# PRoMo_Base_CMS.net
KiCad netlist of a schematic drawn in EAGLE
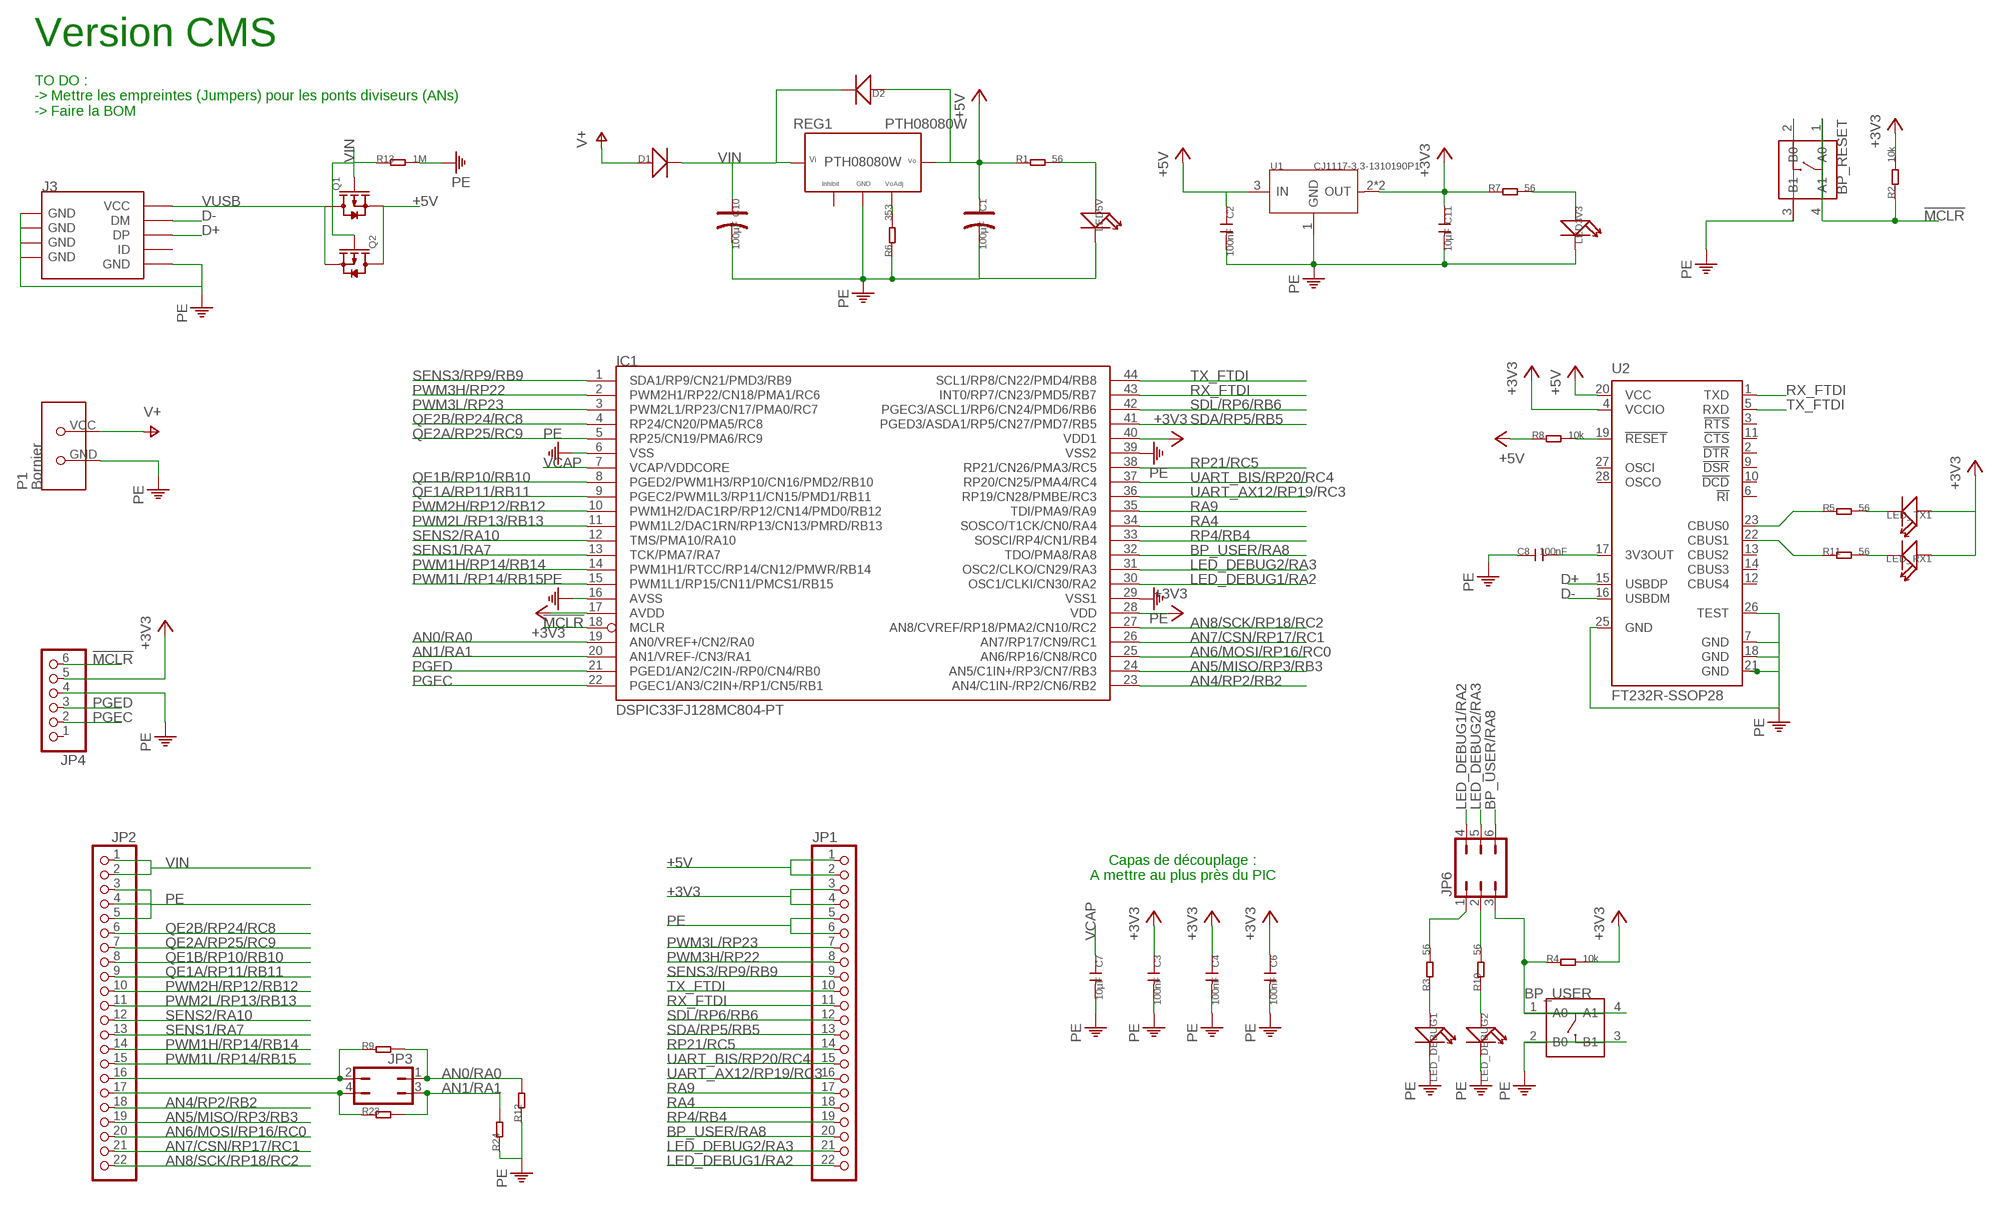
[diagram p0: schematic, sheet 1]

(export (version "E")
  (design (tool "Eeschema 10.0.6"))
  (components
    (comp (ref "BP_RESET")
      (value "BUTTON-4P-6.2X6.2")
      (footprint "eagle-import:4P-6.2X6.2")
      (libsource (lib "eagle-import") (part "BUTTON-4P-6.2X6.2"))
    )
    (comp (ref "BP_USER")
      (value "BUTTON-4P-6.2X6.2")
      (footprint "eagle-import:4P-6.2X6.2")
      (libsource (lib "eagle-import") (part "BUTTON-4P-6.2X6.2"))
    )
    (comp (ref "C1")
      (value "100µF")
      (footprint "eagle-import:ELECTRO-5.3MM")
      (libsource (lib "eagle-import") (part "CAP-D5.3/2.0"))
    )
    (comp (ref "C2")
      (value "100nF")
      (footprint "eagle-import:C0805")
      (libsource (lib "eagle-import") (part "C-0805"))
    )
    (comp (ref "C3")
      (value "100nF")
      (footprint "eagle-import:C0805")
      (libsource (lib "eagle-import") (part "C-0805"))
    )
    (comp (ref "C4")
      (value "100nF")
      (footprint "eagle-import:C0805")
      (libsource (lib "eagle-import") (part "C-0805"))
    )
    (comp (ref "C6")
      (value "100nF")
      (footprint "eagle-import:C0805")
      (libsource (lib "eagle-import") (part "C-0805"))
    )
    (comp (ref "C7")
      (value "10µF")
      (footprint "eagle-import:C0805")
      (libsource (lib "eagle-import") (part "C-0805"))
    )
    (comp (ref "C8")
      (value "100nF")
      (footprint "eagle-import:C0805")
      (libsource (lib "eagle-import") (part "C-0805"))
    )
    (comp (ref "C10")
      (value "100µF")
      (footprint "eagle-import:ELECTRO-5.3MM")
      (libsource (lib "eagle-import") (part "CAP-D5.3/2.0"))
    )
    (comp (ref "C11")
      (value "10µF")
      (footprint "eagle-import:C0805")
      (libsource (lib "eagle-import") (part "C-0805"))
    )
    (comp (ref "D1")
      (value "D'1206'")
      (footprint "eagle-import:SOD123")
      (libsource (lib "eagle-import") (part "D'1206'"))
    )
    (comp (ref "D2")
      (value "D'1206'")
      (footprint "eagle-import:SOD123")
      (libsource (lib "eagle-import") (part "D'1206'"))
    )
    (comp (ref "IC1")
      (value "DSPIC33FJ128MC804-PT")
      (footprint "eagle-import:TQFP44")
      (libsource (lib "eagle-import") (part "DSPIC33FJ128MC804-PT"))
    )
    (comp (ref "J3")
      (value "USB-MINIUSB-5P-TH")
      (footprint "eagle-import:MINI-5P")
      (libsource (lib "eagle-import") (part "USB-MINIUSB-5P-TH"))
    )
    (comp (ref "JP1")
      (value "PINHD-1X22")
      (footprint "eagle-import:1X22")
      (libsource (lib "eagle-import") (part "PINHD-1X22"))
    )
    (comp (ref "JP2")
      (value "PINHD-1X22")
      (footprint "eagle-import:1X22")
      (libsource (lib "eagle-import") (part "PINHD-1X22"))
    )
    (comp (ref "JP3")
      (value "JP2Q")
      (footprint "eagle-import:JP2Q")
      (libsource (lib "eagle-import") (part "JP2Q"))
    )
    (comp (ref "JP4")
      (value "PINHD-1X6/90")
      (footprint "eagle-import:1X06_90")
      (libsource (lib "eagle-import") (part "PINHD-1X6/90"))
    )
    (comp (ref "JP6")
      (value "JP3Q")
      (footprint "eagle-import:JP3Q")
      (libsource (lib "eagle-import") (part "JP3Q"))
    )
    (comp (ref "LED3V3")
      (value "LED'1206'")
      (footprint "eagle-import:LED-1206")
      (libsource (lib "eagle-import") (part "LED'1206'"))
    )
    (comp (ref "LED5V")
      (value "LED'1206'")
      (footprint "eagle-import:LED-1206")
      (libsource (lib "eagle-import") (part "LED'1206'"))
    )
    (comp (ref "LED_DEBUG1")
      (value "LED'1206'")
      (footprint "eagle-import:LED-1206")
      (libsource (lib "eagle-import") (part "LED'1206'"))
    )
    (comp (ref "LED_DEBUG2")
      (value "LED'1206'")
      (footprint "eagle-import:LED-1206")
      (libsource (lib "eagle-import") (part "LED'1206'"))
    )
    (comp (ref "LED_RX1")
      (value "LED'1206'")
      (footprint "eagle-import:LED-1206")
      (libsource (lib "eagle-import") (part "LED'1206'"))
    )
    (comp (ref "LED_TX1")
      (value "LED'1206'")
      (footprint "eagle-import:LED-1206")
      (libsource (lib "eagle-import") (part "LED'1206'"))
    )
    (comp (ref "P1")
      (value "Bornier")
      (footprint "eagle-import:BORNIER_COUDEE_3.5")
      (libsource (lib "eagle-import") (part "BORNIER_3.5MM"))
    )
    (comp (ref "Q1")
      (value "MOSFET-P'SI2323CDS/SI2305DS<BR>'")
      (footprint "eagle-import:SOT23")
      (libsource (lib "eagle-import") (part "MOSFET-P'SI2323CDS/SI2305DS{lt}BR{gt}'"))
    )
    (comp (ref "Q2")
      (value "MOSFET-P'SI2323CDS/SI2305DS<BR>'")
      (footprint "eagle-import:SOT23")
      (libsource (lib "eagle-import") (part "MOSFET-P'SI2323CDS/SI2305DS{lt}BR{gt}'"))
    )
    (comp (ref "R1")
      (value "56")
      (footprint "eagle-import:R0805")
      (libsource (lib "eagle-import") (part "R-0805"))
    )
    (comp (ref "R2")
      (value "10k")
      (footprint "eagle-import:R0805")
      (libsource (lib "eagle-import") (part "R-0805"))
    )
    (comp (ref "R3")
      (value "56")
      (footprint "eagle-import:R0805")
      (libsource (lib "eagle-import") (part "R-0805"))
    )
    (comp (ref "R4")
      (value "10k")
      (footprint "eagle-import:R0805")
      (libsource (lib "eagle-import") (part "R-0805"))
    )
    (comp (ref "R5")
      (value "56")
      (footprint "eagle-import:R0805")
      (libsource (lib "eagle-import") (part "R-0805"))
    )
    (comp (ref "R6")
      (value "353")
      (footprint "eagle-import:R0204_7")
      (libsource (lib "eagle-import") (part "R-0204/7"))
    )
    (comp (ref "R7")
      (value "56")
      (footprint "eagle-import:R0805")
      (libsource (lib "eagle-import") (part "R-0805"))
    )
    (comp (ref "R8")
      (value "10k")
      (footprint "eagle-import:R0805")
      (libsource (lib "eagle-import") (part "R-0805"))
    )
    (comp (ref "R9")
      (value "R-0805")
      (footprint "eagle-import:R0805")
      (libsource (lib "eagle-import") (part "R-0805"))
    )
    (comp (ref "R10")
      (value "56")
      (footprint "eagle-import:R0805")
      (libsource (lib "eagle-import") (part "R-0805"))
    )
    (comp (ref "R11")
      (value "56")
      (footprint "eagle-import:R0805")
      (libsource (lib "eagle-import") (part "R-0805"))
    )
    (comp (ref "R12")
      (value "R-0805")
      (footprint "eagle-import:R0805")
      (libsource (lib "eagle-import") (part "R-0805"))
    )
    (comp (ref "R13")
      (value "1M")
      (footprint "eagle-import:R0805")
      (libsource (lib "eagle-import") (part "R-0805"))
    )
    (comp (ref "R23")
      (value "R-0805")
      (footprint "eagle-import:R0805")
      (libsource (lib "eagle-import") (part "R-0805"))
    )
    (comp (ref "R24")
      (value "R-0805")
      (footprint "eagle-import:R0805")
      (libsource (lib "eagle-import") (part "R-0805"))
    )
    (comp (ref "REG1")
      (value "PTH08080W")
      (footprint "eagle-import:PTH08080W")
      (libsource (lib "eagle-import") (part "PTH08080W"))
    )
    (comp (ref "U1")
      (value "CJ1117-3.3-1310190P1")
      (footprint "eagle-import:SOT223")
      (libsource (lib "eagle-import") (part "CJ1117-3.3-1310190P1"))
    )
    (comp (ref "U2")
      (value "FT232R-SSOP28")
      (footprint "eagle-import:SSOP28")
      (libsource (lib "eagle-import") (part "FT232R-SSOP28"))
    )
  )
  (nets
    (net (code "1") (name "+3V3") (class "Default")
      (node (ref "C11") (pin "1") (pinfunction "1_1") (pintype "passive"))
      (node (ref "C3") (pin "1") (pinfunction "1_1") (pintype "passive"))
      (node (ref "C4") (pin "1") (pinfunction "1_1") (pintype "passive"))
      (node (ref "C6") (pin "1") (pinfunction "1_1") (pintype "passive"))
      (node (ref "IC1") (pin "17") (pinfunction "AVDD_17") (pintype "power_in"))
      (node (ref "IC1") (pin "28") (pinfunction "VDD_28") (pintype "power_in"))
      (node (ref "IC1") (pin "40") (pinfunction "VDD1_40") (pintype "power_in"))
      (node (ref "JP1") (pin "3") (pinfunction "3_3") (pintype "passive"))
      (node (ref "JP1") (pin "4") (pinfunction "4_4") (pintype "passive"))
      (node (ref "JP4") (pin "5") (pinfunction "5_5") (pintype "passive"))
      (node (ref "LED_RX1") (pin "+") (pinfunction "+_+") (pintype "passive"))
      (node (ref "LED_TX1") (pin "+") (pinfunction "+_+") (pintype "passive"))
      (node (ref "R2") (pin "2") (pinfunction "2_2") (pintype "passive"))
      (node (ref "R4") (pin "2") (pinfunction "2_2") (pintype "passive"))
      (node (ref "R7") (pin "1") (pinfunction "1_1") (pintype "passive"))
      (node (ref "U1") (pin "2") (pinfunction "OUT_2") (pintype "bidirectional"))
      (node (ref "U1") (pin "TER") (pinfunction "OUT_TER") (pintype "bidirectional"))
      (node (ref "U2") (pin "4") (pinfunction "VCCIO_4") (pintype "input"))
    )
    (net (code "2") (name "+5V") (class "Default")
      (node (ref "C1") (pin "+") (pinfunction "+_+") (pintype "passive"))
      (node (ref "C2") (pin "1") (pinfunction "1_1") (pintype "passive"))
      (node (ref "D2") (pin "+") (pinfunction "+_+") (pintype "passive"))
      (node (ref "JP1") (pin "1") (pinfunction "1_1") (pintype "passive"))
      (node (ref "JP1") (pin "2") (pinfunction "2_2") (pintype "passive"))
      (node (ref "Q1") (pin "2") (pinfunction "S_2") (pintype "passive"))
      (node (ref "Q2") (pin "3") (pinfunction "D_3") (pintype "passive"))
      (node (ref "R1") (pin "1") (pinfunction "1_1") (pintype "passive"))
      (node (ref "R8") (pin "1") (pinfunction "1_1") (pintype "passive"))
      (node (ref "REG1") (pin "P$3") (pinfunction "3_VO_P$3") (pintype "bidirectional"))
      (node (ref "U1") (pin "3") (pinfunction "IN_3") (pintype "bidirectional"))
      (node (ref "U2") (pin "20") (pinfunction "VCC_20") (pintype "input"))
    )
    (net (code "3") (name "/AN0{slash}RA0") (class "Default")
      (node (ref "IC1") (pin "19") (pinfunction "AN0/VREF+/CN2/RA0_19") (pintype "bidirectional"))
      (node (ref "JP3") (pin "1") (pinfunction "1_1") (pintype "passive"))
      (node (ref "R12") (pin "2") (pinfunction "2_2") (pintype "passive"))
      (node (ref "R9") (pin "2") (pinfunction "2_2") (pintype "passive"))
    )
    (net (code "4") (name "/AN1{slash}RA1") (class "Default")
      (node (ref "IC1") (pin "20") (pinfunction "AN1/VREF-/CN3/RA1_20") (pintype "bidirectional"))
      (node (ref "JP3") (pin "3") (pinfunction "3_3") (pintype "passive"))
      (node (ref "R23") (pin "2") (pinfunction "2_2") (pintype "passive"))
      (node (ref "R24") (pin "2") (pinfunction "2_2") (pintype "passive"))
    )
    (net (code "5") (name "/AN4{slash}RP2{slash}RB2") (class "Default")
      (node (ref "IC1") (pin "23") (pinfunction "AN4/C1IN-/RP2/CN6/RB2_23") (pintype "bidirectional"))
      (node (ref "JP2") (pin "18") (pinfunction "18_18") (pintype "passive"))
    )
    (net (code "6") (name "/AN5{slash}MISO{slash}RP3{slash}RB3") (class "Default")
      (node (ref "IC1") (pin "24") (pinfunction "AN5/C1IN+/RP3/CN7/RB3_24") (pintype "bidirectional"))
      (node (ref "JP2") (pin "19") (pinfunction "19_19") (pintype "passive"))
    )
    (net (code "7") (name "/AN6{slash}MOSI{slash}RP16{slash}RC0") (class "Default")
      (node (ref "IC1") (pin "25") (pinfunction "AN6/RP16/CN8/RC0_25") (pintype "bidirectional"))
      (node (ref "JP2") (pin "20") (pinfunction "20_20") (pintype "passive"))
    )
    (net (code "8") (name "/AN7{slash}CSN{slash}RP17{slash}RC1") (class "Default")
      (node (ref "IC1") (pin "26") (pinfunction "AN7/RP17/CN9/RC1_26") (pintype "bidirectional"))
      (node (ref "JP2") (pin "21") (pinfunction "21_21") (pintype "passive"))
    )
    (net (code "9") (name "/AN8{slash}SCK{slash}RP18{slash}RC2") (class "Default")
      (node (ref "IC1") (pin "27") (pinfunction "AN8/CVREF/RP18/PMA2/CN10/RC2_27") (pintype "bidirectional"))
      (node (ref "JP2") (pin "22") (pinfunction "22_22") (pintype "passive"))
    )
    (net (code "10") (name "/BP_USER{slash}RA8") (class "Default")
      (node (ref "IC1") (pin "32") (pinfunction "TDO/PMA8/RA8_32") (pintype "bidirectional"))
      (node (ref "JP1") (pin "20") (pinfunction "20_20") (pintype "passive"))
      (node (ref "JP6") (pin "6") (pinfunction "6_6") (pintype "passive"))
    )
    (net (code "11") (name "/D+") (class "Default")
      (node (ref "J3") (pin "DP") (pinfunction "DP_DP") (pintype "bidirectional"))
      (node (ref "U2") (pin "15") (pinfunction "USBDP_15") (pintype "input"))
    )
    (net (code "12") (name "/D-") (class "Default")
      (node (ref "J3") (pin "DM") (pinfunction "DM_DM") (pintype "bidirectional"))
      (node (ref "U2") (pin "16") (pinfunction "USBDM_16") (pintype "input"))
    )
    (net (code "13") (name "/LED_DEBUG1{slash}RA2") (class "Default")
      (node (ref "IC1") (pin "30") (pinfunction "OSC1/CLKI/CN30/RA2_30") (pintype "bidirectional"))
      (node (ref "JP1") (pin "22") (pinfunction "22_22") (pintype "passive"))
      (node (ref "JP6") (pin "4") (pinfunction "4_4") (pintype "passive"))
    )
    (net (code "14") (name "/LED_DEBUG2{slash}RA3") (class "Default")
      (node (ref "IC1") (pin "31") (pinfunction "OSC2/CLKO/CN29/RA3_31") (pintype "bidirectional"))
      (node (ref "JP1") (pin "21") (pinfunction "21_21") (pintype "passive"))
      (node (ref "JP6") (pin "5") (pinfunction "5_5") (pintype "passive"))
    )
    (net (code "15") (name "/PGEC") (class "Default")
      (node (ref "IC1") (pin "22") (pinfunction "PGEC1/AN3/C2IN+/RP1/CN5/RB1_22") (pintype "bidirectional"))
      (node (ref "JP4") (pin "2") (pinfunction "2_2") (pintype "passive"))
    )
    (net (code "16") (name "/PGED") (class "Default")
      (node (ref "IC1") (pin "21") (pinfunction "PGED1/AN2/C2IN-/RP0/CN4/RB0_21") (pintype "bidirectional"))
      (node (ref "JP4") (pin "3") (pinfunction "3_3") (pintype "passive"))
    )
    (net (code "17") (name "/PWM1H{slash}RP14{slash}RB14") (class "Default")
      (node (ref "IC1") (pin "14") (pinfunction "PWM1H1/RTCC/RP14/CN12/PMWR/RB14_14") (pintype "bidirectional"))
      (node (ref "JP2") (pin "14") (pinfunction "14_14") (pintype "passive"))
    )
    (net (code "18") (name "/PWM1L{slash}RP14{slash}RB15") (class "Default")
      (node (ref "IC1") (pin "15") (pinfunction "PWM1L1/RP15/CN11/PMCS1/RB15_15") (pintype "bidirectional"))
      (node (ref "JP2") (pin "15") (pinfunction "15_15") (pintype "passive"))
    )
    (net (code "19") (name "/PWM2H{slash}RP12{slash}RB12") (class "Default")
      (node (ref "IC1") (pin "10") (pinfunction "PWM1H2/DAC1RP/RP12/CN14/PMD0/RB12_10") (pintype "bidirectional"))
      (node (ref "JP2") (pin "10") (pinfunction "10_10") (pintype "passive"))
    )
    (net (code "20") (name "/PWM2L{slash}RP13{slash}RB13") (class "Default")
      (node (ref "IC1") (pin "11") (pinfunction "PWM1L2/DAC1RN/RP13/CN13/PMRD/RB13_11") (pintype "bidirectional"))
      (node (ref "JP2") (pin "11") (pinfunction "11_11") (pintype "passive"))
    )
    (net (code "21") (name "/PWM3H{slash}RP22") (class "Default")
      (node (ref "IC1") (pin "2") (pinfunction "PWM2H1/RP22/CN18/PMA1/RC6_2") (pintype "bidirectional"))
      (node (ref "JP1") (pin "8") (pinfunction "8_8") (pintype "passive"))
    )
    (net (code "22") (name "/PWM3L{slash}RP23") (class "Default")
      (node (ref "IC1") (pin "3") (pinfunction "PWM2L1/RP23/CN17/PMA0/RC7_3") (pintype "bidirectional"))
      (node (ref "JP1") (pin "7") (pinfunction "7_7") (pintype "passive"))
    )
    (net (code "23") (name "/QE1A{slash}RP11{slash}RB11") (class "Default")
      (node (ref "IC1") (pin "9") (pinfunction "PGEC2/PWM1L3/RP11/CN15/PMD1/RB11_9") (pintype "bidirectional"))
      (node (ref "JP2") (pin "9") (pinfunction "9_9") (pintype "passive"))
    )
    (net (code "24") (name "/QE1B{slash}RP10{slash}RB10") (class "Default")
      (node (ref "IC1") (pin "8") (pinfunction "PGED2/PWM1H3/RP10/CN16/PMD2/RB10_8") (pintype "bidirectional"))
      (node (ref "JP2") (pin "8") (pinfunction "8_8") (pintype "passive"))
    )
    (net (code "25") (name "/QE2A{slash}RP25{slash}RC9") (class "Default")
      (node (ref "IC1") (pin "5") (pinfunction "RP25/CN19/PMA6/RC9_5") (pintype "bidirectional"))
      (node (ref "JP2") (pin "7") (pinfunction "7_7") (pintype "passive"))
    )
    (net (code "26") (name "/QE2B{slash}RP24{slash}RC8") (class "Default")
      (node (ref "IC1") (pin "4") (pinfunction "RP24/CN20/PMA5/RC8_4") (pintype "bidirectional"))
      (node (ref "JP2") (pin "6") (pinfunction "6_6") (pintype "passive"))
    )
    (net (code "27") (name "/RA4") (class "Default")
      (node (ref "IC1") (pin "34") (pinfunction "SOSCO/T1CK/CN0/RA4_34") (pintype "bidirectional"))
      (node (ref "JP1") (pin "18") (pinfunction "18_18") (pintype "passive"))
    )
    (net (code "28") (name "/RA9") (class "Default")
      (node (ref "IC1") (pin "35") (pinfunction "TDI/PMA9/RA9_35") (pintype "bidirectional"))
      (node (ref "JP1") (pin "17") (pinfunction "17_17") (pintype "passive"))
    )
    (net (code "29") (name "/RP4{slash}RB4") (class "Default")
      (node (ref "IC1") (pin "33") (pinfunction "SOSCI/RP4/CN1/RB4_33") (pintype "bidirectional"))
      (node (ref "JP1") (pin "19") (pinfunction "19_19") (pintype "passive"))
    )
    (net (code "30") (name "/RP21{slash}RC5") (class "Default")
      (node (ref "IC1") (pin "38") (pinfunction "RP21/CN26/PMA3/RC5_38") (pintype "bidirectional"))
      (node (ref "JP1") (pin "14") (pinfunction "14_14") (pintype "passive"))
    )
    (net (code "31") (name "/RX_FTDI") (class "Default")
      (node (ref "IC1") (pin "43") (pinfunction "INT0/RP7/CN23/PMD5/RB7_43") (pintype "bidirectional"))
      (node (ref "JP1") (pin "11") (pinfunction "11_11") (pintype "passive"))
      (node (ref "U2") (pin "1") (pinfunction "TXD_1") (pintype "input"))
    )
    (net (code "32") (name "/SDA{slash}RP5{slash}RB5") (class "Default")
      (node (ref "IC1") (pin "41") (pinfunction "PGED3/ASDA1/RP5/CN27/PMD7/RB5_41") (pintype "bidirectional"))
      (node (ref "JP1") (pin "13") (pinfunction "13_13") (pintype "passive"))
    )
    (net (code "33") (name "/SDL{slash}RP6{slash}RB6") (class "Default")
      (node (ref "IC1") (pin "42") (pinfunction "PGEC3/ASCL1/RP6/CN24/PMD6/RB6_42") (pintype "bidirectional"))
      (node (ref "JP1") (pin "12") (pinfunction "12_12") (pintype "passive"))
    )
    (net (code "34") (name "/SENS1{slash}RA7") (class "Default")
      (node (ref "IC1") (pin "13") (pinfunction "TCK/PMA7/RA7_13") (pintype "bidirectional"))
      (node (ref "JP2") (pin "13") (pinfunction "13_13") (pintype "passive"))
    )
    (net (code "35") (name "/SENS2{slash}RA10") (class "Default")
      (node (ref "IC1") (pin "12") (pinfunction "TMS/PMA10/RA10_12") (pintype "bidirectional"))
      (node (ref "JP2") (pin "12") (pinfunction "12_12") (pintype "passive"))
    )
    (net (code "36") (name "/SENS3{slash}RP9{slash}RB9") (class "Default")
      (node (ref "IC1") (pin "1") (pinfunction "SDA1/RP9/CN21/PMD3/RB9_1") (pintype "bidirectional"))
      (node (ref "JP1") (pin "9") (pinfunction "9_9") (pintype "passive"))
    )
    (net (code "37") (name "/TX_FTDI") (class "Default")
      (node (ref "IC1") (pin "44") (pinfunction "SCL1/RP8/CN22/PMD4/RB8_44") (pintype "bidirectional"))
      (node (ref "JP1") (pin "10") (pinfunction "10_10") (pintype "passive"))
      (node (ref "U2") (pin "5") (pinfunction "RXD_5") (pintype "input"))
    )
    (net (code "38") (name "/UART_AX12{slash}RP19{slash}RC3") (class "Default")
      (node (ref "IC1") (pin "36") (pinfunction "RP19/CN28/PMBE/RC3_36") (pintype "bidirectional"))
      (node (ref "JP1") (pin "16") (pinfunction "16_16") (pintype "passive"))
    )
    (net (code "39") (name "/UART_BIS{slash}RP20{slash}RC4") (class "Default")
      (node (ref "IC1") (pin "37") (pinfunction "RP20/CN25/PMA4/RC4_37") (pintype "bidirectional"))
      (node (ref "JP1") (pin "15") (pinfunction "15_15") (pintype "passive"))
    )
    (net (code "40") (name "/VCAP") (class "Default")
      (node (ref "C7") (pin "1") (pinfunction "1_1") (pintype "passive"))
      (node (ref "IC1") (pin "7") (pinfunction "VCAP/VDDCORE_7") (pintype "power_in"))
    )
    (net (code "41") (name "/VIN") (class "Default")
      (node (ref "C10") (pin "+") (pinfunction "+_+") (pintype "passive"))
      (node (ref "D1") (pin "-") (pinfunction "-_-") (pintype "passive"))
      (node (ref "D2") (pin "-") (pinfunction "-_-") (pintype "passive"))
      (node (ref "JP2") (pin "1") (pinfunction "1_1") (pintype "passive"))
      (node (ref "JP2") (pin "2") (pinfunction "2_2") (pintype "passive"))
      (node (ref "Q1") (pin "1") (pinfunction "G_1") (pintype "passive"))
      (node (ref "Q2") (pin "1") (pinfunction "G_1") (pintype "passive"))
      (node (ref "R13") (pin "1") (pinfunction "1_1") (pintype "passive"))
      (node (ref "REG1") (pin "P$1") (pinfunction "1_VI_P$1") (pintype "bidirectional"))
    )
    (net (code "42") (name "/VUSB") (class "Default")
      (node (ref "J3") (pin "VCC") (pinfunction "VCC_VCC") (pintype "bidirectional"))
      (node (ref "Q1") (pin "3") (pinfunction "D_3") (pintype "passive"))
      (node (ref "Q2") (pin "2") (pinfunction "S_2") (pintype "passive"))
    )
    (net (code "43") (name "/~{MCLR}") (class "Default")
      (node (ref "BP_RESET") (pin "1") (pinfunction "A0_1") (pintype "bidirectional"))
      (node (ref "BP_RESET") (pin "4") (pinfunction "A1_4") (pintype "bidirectional"))
      (node (ref "IC1") (pin "18") (pinfunction "MCLR_18") (pintype "input"))
      (node (ref "JP4") (pin "6") (pinfunction "6_6") (pintype "passive"))
      (node (ref "R2") (pin "1") (pinfunction "1_1") (pintype "passive"))
    )
    (net (code "44") (name "Net-(BP_USER-A0)") (class "Default")
      (node (ref "BP_USER") (pin "1") (pinfunction "A0_1") (pintype "bidirectional"))
      (node (ref "BP_USER") (pin "4") (pinfunction "A1_4") (pintype "bidirectional"))
      (node (ref "JP6") (pin "3") (pinfunction "3_3") (pintype "passive"))
      (node (ref "R4") (pin "1") (pinfunction "1_1") (pintype "passive"))
    )
    (net (code "45") (name "Net-(JP2-Pad16)") (class "Default")
      (node (ref "JP2") (pin "16") (pinfunction "16_16") (pintype "passive"))
      (node (ref "JP3") (pin "2") (pinfunction "2_2") (pintype "passive"))
      (node (ref "R9") (pin "1") (pinfunction "1_1") (pintype "passive"))
    )
    (net (code "46") (name "Net-(JP2-Pad17)") (class "Default")
      (node (ref "JP2") (pin "17") (pinfunction "17_17") (pintype "passive"))
      (node (ref "JP3") (pin "4") (pinfunction "4_4") (pintype "passive"))
      (node (ref "R23") (pin "1") (pinfunction "1_1") (pintype "passive"))
    )
    (net (code "47") (name "Net-(JP6-Pad1)") (class "Default")
      (node (ref "JP6") (pin "1") (pinfunction "1_1") (pintype "passive"))
      (node (ref "R3") (pin "2") (pinfunction "2_2") (pintype "passive"))
    )
    (net (code "48") (name "Net-(JP6-Pad2)") (class "Default")
      (node (ref "JP6") (pin "2") (pinfunction "2_2") (pintype "passive"))
      (node (ref "R10") (pin "2") (pinfunction "2_2") (pintype "passive"))
    )
    (net (code "49") (name "Net-(LED3V3-Pad+)") (class "Default")
      (node (ref "LED3V3") (pin "+") (pinfunction "+_+") (pintype "passive"))
      (node (ref "R7") (pin "2") (pinfunction "2_2") (pintype "passive"))
    )
    (net (code "50") (name "Net-(LED5V-Pad+)") (class "Default")
      (node (ref "LED5V") (pin "+") (pinfunction "+_+") (pintype "passive"))
      (node (ref "R1") (pin "2") (pinfunction "2_2") (pintype "passive"))
    )
    (net (code "51") (name "Net-(LED_DEBUG1-Pad+)") (class "Default")
      (node (ref "LED_DEBUG1") (pin "+") (pinfunction "+_+") (pintype "passive"))
      (node (ref "R3") (pin "1") (pinfunction "1_1") (pintype "passive"))
    )
    (net (code "52") (name "Net-(LED_DEBUG2-Pad+)") (class "Default")
      (node (ref "LED_DEBUG2") (pin "+") (pinfunction "+_+") (pintype "passive"))
      (node (ref "R10") (pin "1") (pinfunction "1_1") (pintype "passive"))
    )
    (net (code "53") (name "Net-(LED_RX1-Pad-)") (class "Default")
      (node (ref "LED_RX1") (pin "-") (pinfunction "-_-") (pintype "passive"))
      (node (ref "R11") (pin "2") (pinfunction "2_2") (pintype "passive"))
    )
    (net (code "54") (name "Net-(LED_TX1-Pad-)") (class "Default")
      (node (ref "LED_TX1") (pin "-") (pinfunction "-_-") (pintype "passive"))
      (node (ref "R5") (pin "2") (pinfunction "2_2") (pintype "passive"))
    )
    (net (code "55") (name "Net-(REG1-4_VOADJ)") (class "Default")
      (node (ref "R6") (pin "2") (pinfunction "2_2") (pintype "passive"))
      (node (ref "REG1") (pin "P$4") (pinfunction "4_VOADJ_P$4") (pintype "bidirectional"))
    )
    (net (code "56") (name "Net-(U2-3V3OUT)") (class "Default")
      (node (ref "C8") (pin "2") (pinfunction "2_2") (pintype "passive"))
      (node (ref "U2") (pin "17") (pinfunction "3V3OUT_17") (pintype "input"))
    )
    (net (code "57") (name "Net-(U2-CBUS0)") (class "Default")
      (node (ref "R5") (pin "1") (pinfunction "1_1") (pintype "passive"))
      (node (ref "U2") (pin "23") (pinfunction "CBUS0_23") (pintype "input"))
    )
    (net (code "58") (name "Net-(U2-CBUS1)") (class "Default")
      (node (ref "R11") (pin "1") (pinfunction "1_1") (pintype "passive"))
      (node (ref "U2") (pin "22") (pinfunction "CBUS1_22") (pintype "input"))
    )
    (net (code "59") (name "Net-(U2-~{RESET})") (class "Default")
      (node (ref "R8") (pin "2") (pinfunction "2_2") (pintype "passive"))
      (node (ref "U2") (pin "19") (pinfunction "~{RESET}_19") (pintype "input"))
    )
    (net (code "60") (name "PE") (class "Default")
      (node (ref "BP_RESET") (pin "2") (pinfunction "B0_2") (pintype "bidirectional"))
      (node (ref "BP_RESET") (pin "3") (pinfunction "B1_3") (pintype "bidirectional"))
      (node (ref "BP_USER") (pin "2") (pinfunction "B0_2") (pintype "bidirectional"))
      (node (ref "BP_USER") (pin "3") (pinfunction "B1_3") (pintype "bidirectional"))
      (node (ref "C1") (pin "-") (pinfunction "-_-") (pintype "passive"))
      (node (ref "C10") (pin "-") (pinfunction "-_-") (pintype "passive"))
      (node (ref "C11") (pin "2") (pinfunction "2_2") (pintype "passive"))
      (node (ref "C2") (pin "2") (pinfunction "2_2") (pintype "passive"))
      (node (ref "C3") (pin "2") (pinfunction "2_2") (pintype "passive"))
      (node (ref "C4") (pin "2") (pinfunction "2_2") (pintype "passive"))
      (node (ref "C6") (pin "2") (pinfunction "2_2") (pintype "passive"))
      (node (ref "C7") (pin "2") (pinfunction "2_2") (pintype "passive"))
      (node (ref "C8") (pin "1") (pinfunction "1_1") (pintype "passive"))
      (node (ref "IC1") (pin "16") (pinfunction "AVSS_16") (pintype "power_in"))
      (node (ref "IC1") (pin "29") (pinfunction "VSS1_29") (pintype "power_in"))
      (node (ref "IC1") (pin "39") (pinfunction "VSS2_39") (pintype "power_in"))
      (node (ref "IC1") (pin "6") (pinfunction "VSS_6") (pintype "power_in"))
      (node (ref "J3") (pin "GND") (pinfunction "GND_GND") (pintype "bidirectional"))
      (node (ref "J3") (pin "S1") (pinfunction "GND_S1") (pintype "bidirectional"))
      (node (ref "J3") (pin "S2") (pinfunction "GND_S2") (pintype "bidirectional"))
      (node (ref "J3") (pin "S3") (pinfunction "GND_S3") (pintype "bidirectional"))
      (node (ref "J3") (pin "S4") (pinfunction "GND_S4") (pintype "bidirectional"))
      (node (ref "JP1") (pin "5") (pinfunction "5_5") (pintype "passive"))
      (node (ref "JP1") (pin "6") (pinfunction "6_6") (pintype "passive"))
      (node (ref "JP2") (pin "3") (pinfunction "3_3") (pintype "passive"))
      (node (ref "JP2") (pin "4") (pinfunction "4_4") (pintype "passive"))
      (node (ref "JP2") (pin "5") (pinfunction "5_5") (pintype "passive"))
      (node (ref "JP4") (pin "4") (pinfunction "4_4") (pintype "passive"))
      (node (ref "LED3V3") (pin "-") (pinfunction "-_-") (pintype "passive"))
      (node (ref "LED5V") (pin "-") (pinfunction "-_-") (pintype "passive"))
      (node (ref "LED_DEBUG1") (pin "-") (pinfunction "-_-") (pintype "passive"))
      (node (ref "LED_DEBUG2") (pin "-") (pinfunction "-_-") (pintype "passive"))
      (node (ref "P1") (pin "GND") (pinfunction "GND_GND") (pintype "bidirectional"))
      (node (ref "R12") (pin "1") (pinfunction "1_1") (pintype "passive"))
      (node (ref "R13") (pin "2") (pinfunction "2_2") (pintype "passive"))
      (node (ref "R24") (pin "1") (pinfunction "1_1") (pintype "passive"))
      (node (ref "R6") (pin "1") (pinfunction "1_1") (pintype "passive"))
      (node (ref "REG1") (pin "P$2") (pinfunction "2_GND_P$2") (pintype "bidirectional"))
      (node (ref "U1") (pin "1") (pinfunction "GND_1") (pintype "bidirectional"))
      (node (ref "U2") (pin "18") (pinfunction "GND_18") (pintype "input"))
      (node (ref "U2") (pin "21") (pinfunction "GND_21") (pintype "input"))
      (node (ref "U2") (pin "25") (pinfunction "GND_25") (pintype "input"))
      (node (ref "U2") (pin "26") (pinfunction "TEST_26") (pintype "input"))
      (node (ref "U2") (pin "7") (pinfunction "GND_7") (pintype "input"))
    )
    (net (code "61") (name "V+") (class "Default")
      (node (ref "D1") (pin "+") (pinfunction "+_+") (pintype "passive"))
      (node (ref "P1") (pin "VCC") (pinfunction "VCC_VCC") (pintype "bidirectional"))
    )
    (net (code "62") (name "unconnected-(J3-PadID)") (class "Default")
      (node (ref "J3") (pin "ID") (pinfunction "ID_ID") (pintype "bidirectional"))
    )
    (net (code "63") (name "unconnected-(JP4-Pad1)") (class "Default")
      (node (ref "JP4") (pin "1") (pinfunction "1_1") (pintype "passive"))
    )
    (net (code "64") (name "unconnected-(REG1-5_INHIBIT-PadP$5)") (class "Default")
      (node (ref "REG1") (pin "P$5") (pinfunction "5_INHIBIT_P$5") (pintype "bidirectional"))
    )
    (net (code "65") (name "unconnected-(U2-CBUS2-Pad13)") (class "Default")
      (node (ref "U2") (pin "13") (pinfunction "CBUS2_13") (pintype "input"))
    )
    (net (code "66") (name "unconnected-(U2-CBUS3-Pad14)") (class "Default")
      (node (ref "U2") (pin "14") (pinfunction "CBUS3_14") (pintype "input"))
    )
    (net (code "67") (name "unconnected-(U2-CBUS4-Pad12)") (class "Default")
      (node (ref "U2") (pin "12") (pinfunction "CBUS4_12") (pintype "input"))
    )
    (net (code "68") (name "unconnected-(U2-OSCI-Pad27)") (class "Default")
      (node (ref "U2") (pin "27") (pinfunction "OSCI_27") (pintype "input"))
    )
    (net (code "69") (name "unconnected-(U2-OSCO-Pad28)") (class "Default")
      (node (ref "U2") (pin "28") (pinfunction "OSCO_28") (pintype "input"))
    )
    (net (code "70") (name "unconnected-(U2-~{CTS}-Pad11)") (class "Default")
      (node (ref "U2") (pin "11") (pinfunction "~{CTS}_11") (pintype "input"))
    )
    (net (code "71") (name "unconnected-(U2-~{DCD}-Pad10)") (class "Default")
      (node (ref "U2") (pin "10") (pinfunction "~{DCD}_10") (pintype "input"))
    )
    (net (code "72") (name "unconnected-(U2-~{DSR}-Pad9)") (class "Default")
      (node (ref "U2") (pin "9") (pinfunction "~{DSR}_9") (pintype "input"))
    )
    (net (code "73") (name "unconnected-(U2-~{DTR}-Pad2)") (class "Default")
      (node (ref "U2") (pin "2") (pinfunction "~{DTR}_2") (pintype "input"))
    )
    (net (code "74") (name "unconnected-(U2-~{RI}-Pad6)") (class "Default")
      (node (ref "U2") (pin "6") (pinfunction "~{RI}_6") (pintype "input"))
    )
    (net (code "75") (name "unconnected-(U2-~{RTS}-Pad3)") (class "Default")
      (node (ref "U2") (pin "3") (pinfunction "~{RTS}_3") (pintype "input"))
    )
  )
)
